# Microcontroleur.net
KiCad netlist of a schematic drawn in Altium Designer
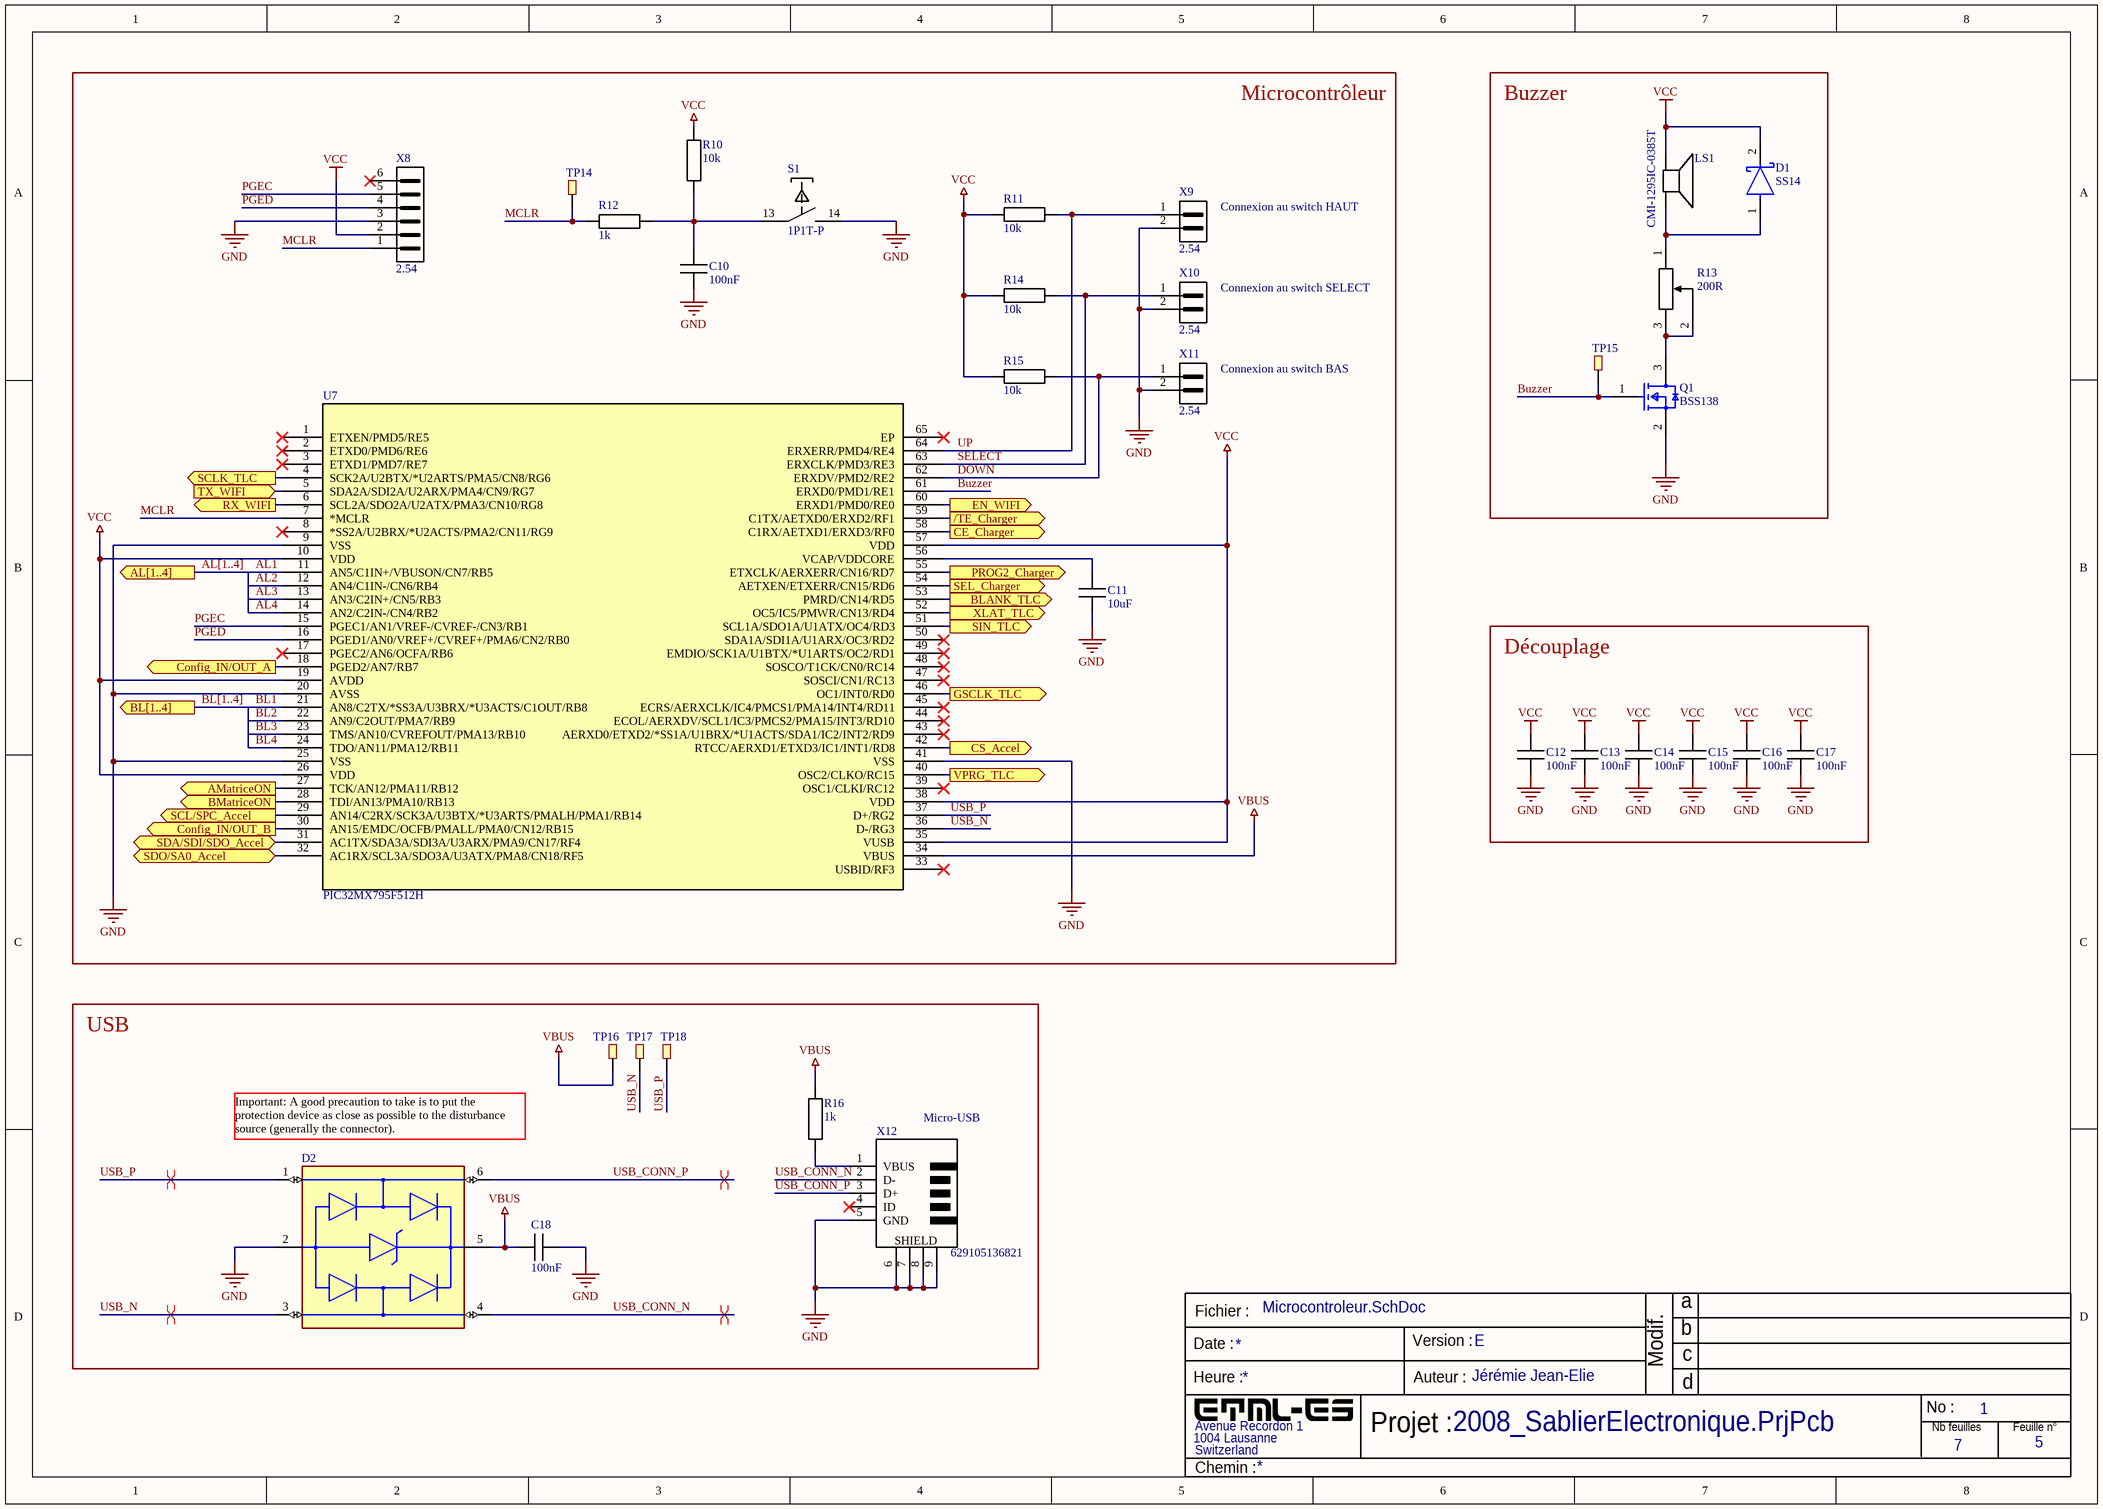
[diagram p0: Microcontroleur.SchDoc]

(export (version "E")
  (design (tool "Eeschema 10.0.6"))
  (components
    (comp (ref "C10")
      (value "100nF")
      (footprint "CAPC1608X08M")
      (description "CAPC 100nF X7R 50V 10% 1608 (0603 INCH)")
      (fields (field (name "VOLTAGE") "50V") (field (name "MANUFACTURER") "TDK"))
      (libsource (lib "ETML-ES") (part "CAP"))
    )
    (comp (ref "C11")
      (value "10uF")
      (footprint "CAPC1608X08M")
      (description "CAPC 10uF X5R 10V 20% 1608 (0603 INCH)")
      (fields (field (name "TOLERANCE") "±20%") (field (name "MANUFACTURER") "TDK"))
      (libsource (lib "ETML-ES") (part "CAP"))
    )
    (comp (ref "C12")
      (value "100nF")
      (footprint "CAPC1608X08M")
      (description "CAPC 100nF X7R 50V 10% 1608 (0603 INCH)")
      (fields (field (name "VOLTAGE") "50V") (field (name "MANUFACTURER") "TDK"))
      (libsource (lib "ETML-ES") (part "CAP"))
    )
    (comp (ref "C13")
      (value "100nF")
      (footprint "CAPC1608X08M")
      (description "CAPC 100nF X7R 50V 10% 1608 (0603 INCH)")
      (fields (field (name "VOLTAGE") "50V") (field (name "MANUFACTURER") "TDK"))
      (libsource (lib "ETML-ES") (part "CAP"))
    )
    (comp (ref "C14")
      (value "100nF")
      (footprint "CAPC1608X08M")
      (description "CAPC 100nF X7R 50V 10% 1608 (0603 INCH)")
      (fields (field (name "VOLTAGE") "50V") (field (name "MANUFACTURER") "TDK"))
      (libsource (lib "ETML-ES") (part "CAP"))
    )
    (comp (ref "C15")
      (value "100nF")
      (footprint "CAPC1608X08M")
      (description "CAPC 100nF X7R 50V 10% 1608 (0603 INCH)")
      (fields (field (name "VOLTAGE") "50V") (field (name "MANUFACTURER") "TDK"))
      (libsource (lib "ETML-ES") (part "CAP"))
    )
    (comp (ref "C16")
      (value "100nF")
      (footprint "CAPC1608X08M")
      (description "CAPC 100nF X7R 50V 10% 1608 (0603 INCH)")
      (fields (field (name "VOLTAGE") "50V") (field (name "MANUFACTURER") "TDK"))
      (libsource (lib "ETML-ES") (part "CAP"))
    )
    (comp (ref "C17")
      (value "100nF")
      (footprint "CAPC1608X08M")
      (description "CAPC 100nF X7R 50V 10% 1608 (0603 INCH)")
      (fields (field (name "VOLTAGE") "50V") (field (name "MANUFACTURER") "TDK"))
      (libsource (lib "ETML-ES") (part "CAP"))
    )
    (comp (ref "C18")
      (value "100nF")
      (footprint "CAPC1608X08M")
      (description "CAPC 100nF X7R 50V 10% 1608 (0603 INCH)")
      (fields (field (name "VOLTAGE") "50V") (field (name "MANUFACTURER") "TDK"))
      (libsource (lib "ETML-ES") (part "CAP"))
    )
    (comp (ref "D1")
      (value "SS14")
      (footprint "FP-403AE-MFG")
      (description "DIODE SCHOTTKY 40V 1A SMA")
      (fields
        (field (name "MANUFACTURER") "ON Semiconductor")
        (field (name "OCTOPART") "https://octopart.com/ss14-on+semiconductor-29205033")
      )
      (libsource (lib "Altium Content Vault") (part "360ad2f4ac25a952324d13796385471"))
    )
    (comp (ref "D2")
      (value "USBLC6-2P6")
      (footprint "SOT95P280X145-6N")
      (libsource (lib "2008_SablierElectronique_SCHLIB") (part "USBLC6-2P6"))
    )
    (comp (ref "LS1")
      (value "CMI-1295IC-0385T")
      (footprint "CMI-1295IC-0385T")
      (description "12 mm, 3 Vdc, 85 dB, Through Hole, Driving Circuit, Magnetic Audio Indicator Buzzer")
      (libsource (lib "Schlib1") (part "CMI-1295IC-0385T"))
    )
    (comp (ref "Q1")
      (value "BSS138")
      (footprint "FP-318-08-IPC_B")
      (description "MOSFET N-CH 50V 220MA SOT-23")
      (libsource (lib "Altium Content Vault") (part "3b9c635fedb024a5347a57b145af9cc"))
    )
    (comp (ref "R10")
      (value "10k")
      (footprint "RESC1608X06M")
      (description "RES 10kohm  ±1% 0.1W  1608 (0603 INCH)")
      (fields (field (name "TOLERANCE") "±1%") (field (name "VOLTAGE") "75V"))
      (libsource (lib "ETML-ES") (part "RES"))
    )
    (comp (ref "R11")
      (value "10k")
      (footprint "RESC1608X06M")
      (description "RES 10kohm  ±1% 0.1W  1608 (0603 INCH)")
      (fields (field (name "TOLERANCE") "±1%") (field (name "VOLTAGE") "75V"))
      (libsource (lib "ETML-ES") (part "RES"))
    )
    (comp (ref "R12")
      (value "1k")
      (footprint "RESC1608X06M")
      (description "RES 1.0kohm  ±1% 0.1W  1608 (0603 INCH)")
      (fields (field (name "POWER") "0.1W") (field (name "TOLERANCE") "±1%"))
      (libsource (lib "ETML-ES") (part "RES"))
    )
    (comp (ref "R13") (value "200R") (footprint "POT_200r") (libsource (lib "Schlib1") (part "Pot_200R")))
    (comp (ref "R14")
      (value "10k")
      (footprint "RESC1608X06M")
      (description "RES 10kohm  ±1% 0.1W  1608 (0603 INCH)")
      (fields (field (name "TOLERANCE") "±1%") (field (name "VOLTAGE") "75V"))
      (libsource (lib "ETML-ES") (part "RES"))
    )
    (comp (ref "R15")
      (value "10k")
      (footprint "RESC1608X06M")
      (description "RES 10kohm  ±1% 0.1W  1608 (0603 INCH)")
      (fields (field (name "TOLERANCE") "±1%") (field (name "VOLTAGE") "75V"))
      (libsource (lib "ETML-ES") (part "RES"))
    )
    (comp (ref "R16")
      (value "1k")
      (footprint "RESC1608X06M")
      (description "RES 1.0kohm  ±1% 0.1W  1608 (0603 INCH)")
      (fields (field (name "POWER") "0.1W") (field (name "TOLERANCE") "±1%"))
      (libsource (lib "ETML-ES") (part "RES"))
    )
    (comp (ref "S1")
      (value "1P1T-P")
      (footprint "TE_1825910-6")
      (description "SW 600X600X500 24V 50mA THT")
      (fields (field (name "VOLTAGE") "24V") (field (name "MANUFACTURER") "TE Connectivity"))
      (libsource (lib "ETML-ES") (part "SWI-1P1T-P"))
    )
    (comp (ref "TP14")
      (value "TestPoint")
      (footprint "KEYSTONE_5019")
      (libsource (lib "Schlib1") (part "TestPoint"))
    )
    (comp (ref "TP15")
      (value "TestPoint")
      (footprint "KEYSTONE_5019")
      (libsource (lib "Schlib1") (part "TestPoint"))
    )
    (comp (ref "TP16")
      (value "TestPoint")
      (footprint "KEYSTONE_5019")
      (libsource (lib "Schlib1") (part "TestPoint"))
    )
    (comp (ref "TP17")
      (value "TestPoint")
      (footprint "KEYSTONE_5019")
      (libsource (lib "Schlib1") (part "TestPoint"))
    )
    (comp (ref "TP18")
      (value "TestPoint")
      (footprint "KEYSTONE_5019")
      (libsource (lib "Schlib1") (part "TestPoint"))
    )
    (comp (ref "U7")
      (value "PIC32MX795F512H")
      (footprint "TQFP64_10x10MC_MCH")
      (libsource (lib "Schlib1") (part "PIC32MX795F512H"))
    )
    (comp (ref "X8")
      (value "2.54")
      (footprint "PIN-1x06-2.54")
      (description "PIN HEADER 2.54 1x06")
      (fields (field (name "MANUFACTURER") "Würth Electronik") (field (name "VOLTAGE") "250V"))
      (libsource (lib "ETML-ES") (part "CON-PIN-1x06"))
    )
    (comp (ref "X9")
      (value "2.54")
      (footprint "PIN-1x02-2.54")
      (description "PIN HEADER 2.54 1x02")
      (fields (field (name "MANUFACTURER") "Würth Electronik") (field (name "VOLTAGE") "250V"))
      (libsource (lib "ETML-ES") (part "CON-PIN-1x02"))
    )
    (comp (ref "X10")
      (value "2.54")
      (footprint "PIN-1x02-2.54")
      (description "PIN HEADER 2.54 1x02")
      (fields (field (name "MANUFACTURER") "Würth Electronik") (field (name "VOLTAGE") "250V"))
      (libsource (lib "ETML-ES") (part "CON-PIN-1x02"))
    )
    (comp (ref "X11")
      (value "2.54")
      (footprint "PIN-1x02-2.54")
      (description "PIN HEADER 2.54 1x02")
      (fields (field (name "MANUFACTURER") "Würth Electronik") (field (name "VOLTAGE") "250V"))
      (libsource (lib "ETML-ES") (part "CON-PIN-1x02"))
    )
    (comp (ref "X12")
      (value "629105136821")
      (footprint "WE_629105136821")
      (description "USB MICRO 5P Horizontal SMT")
      (fields (field (name "MANUFACTURER") "Würth Electronik"))
      (libsource (lib "ETML-ES") (part "USB_MINI_MICRO_B_F"))
    )
  )
  (nets
    (net (code "1") (name "/AL1") (class "Default")
      (node (ref "U7") (pin "11") (pinfunction "AN5/C1IN+/VBUSON/CN7/RB5_11") (pintype "passive"))
    )
    (net (code "2") (name "/AL2") (class "Default")
      (node (ref "U7") (pin "12") (pinfunction "AN4/C1IN-/CN6/RB4_12") (pintype "passive"))
    )
    (net (code "3") (name "/AL3") (class "Default")
      (node (ref "U7") (pin "13") (pinfunction "AN3/C2IN+/CN5/RB3_13") (pintype "passive"))
    )
    (net (code "4") (name "/AL4") (class "Default")
      (node (ref "U7") (pin "14") (pinfunction "AN2/C2IN-/CN4/RB2_14") (pintype "passive"))
    )
    (net (code "6") (name "/AMatriceON") (class "Default")
      (node (ref "U7") (pin "27") (pinfunction "TCK/AN12/PMA11/RB12_27") (pintype "passive"))
    )
    (net (code "7") (name "/BL1") (class "Default")
      (node (ref "U7") (pin "21") (pinfunction "AN8/C2TX/*SS3A/U3BRX/*U3ACTS/C1OUT/RB8_21") (pintype "passive"))
    )
    (net (code "8") (name "/BL2") (class "Default")
      (node (ref "U7") (pin "22") (pinfunction "AN9/C2OUT/PMA7/RB9_22") (pintype "passive"))
    )
    (net (code "9") (name "/BL3") (class "Default")
      (node (ref "U7") (pin "23") (pinfunction "TMS/AN10/CVREFOUT/PMA13/RB10_23") (pintype "passive"))
    )
    (net (code "10") (name "/BL4") (class "Default")
      (node (ref "U7") (pin "24") (pinfunction "TDO/AN11/PMA12/RB11_24") (pintype "passive"))
    )
    (net (code "11") (name "/BLANK_TLC") (class "Default")
      (node (ref "U7") (pin "53") (pinfunction "PMRD/CN14/RD5_53") (pintype "passive"))
    )
    (net (code "13") (name "/BMatriceON") (class "Default")
      (node (ref "U7") (pin "28") (pinfunction "TDI/AN13/PMA10/RB13_28") (pintype "passive"))
    )
    (net (code "14") (name "/Buzzer") (class "Default")
      (node (ref "Q1") (pin "1") (pinfunction "G_1") (pintype "passive"))
      (node (ref "TP15") (pin "1") (pinfunction "1_1") (pintype "passive"))
      (node (ref "U7") (pin "61") (pinfunction "ERXD0/PMD1/RE1_61") (pintype "passive"))
    )
    (net (code "15") (name "/CE_Charger") (class "Default")
      (node (ref "U7") (pin "58") (pinfunction "C1RX/AETXD1/ERXD3/RF0_58") (pintype "passive"))
    )
    (net (code "16") (name "/CS_Accel") (class "Default")
      (node (ref "U7") (pin "42") (pinfunction "RTCC/AERXD1/ETXD3/IC1/INT1/RD8_42") (pintype "passive"))
    )
    (net (code "17") (name "/Config_IN{slash}OUT_A") (class "Default")
      (node (ref "U7") (pin "18") (pinfunction "PGED2/AN7/RB7_18") (pintype "passive"))
    )
    (net (code "18") (name "/Config_IN{slash}OUT_B") (class "Default")
      (node (ref "U7") (pin "30") (pinfunction "AN15/EMDC/OCFB/PMALL/PMA0/CN12/RB15_30") (pintype "passive"))
    )
    (net (code "19") (name "/DOWN") (class "Default")
      (node (ref "R15") (pin "1") (pinfunction "1_1") (pintype "passive"))
      (node (ref "U7") (pin "62") (pinfunction "ERXDV/PMD2/RE2_62") (pintype "passive"))
      (node (ref "X11") (pin "1") (pinfunction "1_1") (pintype "passive"))
    )
    (net (code "20") (name "/EN_WIFI") (class "Default")
      (node (ref "U7") (pin "60") (pinfunction "ERXD1/PMD0/RE0_60") (pintype "passive"))
    )
    (net (code "21") (name "/GSCLK_TLC") (class "Default")
      (node (ref "U7") (pin "46") (pinfunction "OC1/INT0/RD0_46") (pintype "passive"))
    )
    (net (code "22") (name "/MCLR") (class "Default")
      (node (ref "R12") (pin "1") (pinfunction "1_1") (pintype "passive"))
      (node (ref "TP14") (pin "1") (pinfunction "1_1") (pintype "passive"))
      (node (ref "U7") (pin "7") (pinfunction "*MCLR_7") (pintype "passive"))
      (node (ref "X8") (pin "1") (pinfunction "1_1") (pintype "passive"))
    )
    (net (code "23") (name "/PGEC") (class "Default")
      (node (ref "U7") (pin "15") (pinfunction "PGEC1/AN1/VREF-/CVREF-/CN3/RB1_15") (pintype "passive"))
      (node (ref "X8") (pin "5") (pinfunction "5_5") (pintype "passive"))
    )
    (net (code "24") (name "/PGED") (class "Default")
      (node (ref "U7") (pin "16") (pinfunction "PGED1/AN0/VREF+/CVREF+/PMA6/CN2/RB0_16") (pintype "passive"))
      (node (ref "X8") (pin "4") (pinfunction "4_4") (pintype "passive"))
    )
    (net (code "25") (name "/PROG2_Charger") (class "Default")
      (node (ref "U7") (pin "55") (pinfunction "ETXCLK/AERXERR/CN16/RD7_55") (pintype "passive"))
    )
    (net (code "26") (name "/RX_WIFI") (class "Default")
      (node (ref "U7") (pin "6") (pinfunction "SCL2A/SDO2A/U2ATX/PMA3/CN10/RG8_6") (pintype "passive"))
    )
    (net (code "27") (name "/SCLK_TLC") (class "Default")
      (node (ref "U7") (pin "4") (pinfunction "SCK2A/U2BTX/*U2ARTS/PMA5/CN8/RG6_4") (pintype "passive"))
    )
    (net (code "28") (name "/SCL{slash}SPC_Accel") (class "Default")
      (node (ref "U7") (pin "29") (pinfunction "AN14/C2RX/SCK3A/U3BTX/*U3ARTS/PMALH/PMA1/RB14_29") (pintype "passive"))
    )
    (net (code "29") (name "/SDA{slash}SDI{slash}SDO_Accel") (class "Default")
      (node (ref "U7") (pin "31") (pinfunction "AC1TX/SDA3A/SDI3A/U3ARX/PMA9/CN17/RF4_31") (pintype "passive"))
    )
    (net (code "30") (name "/SDO{slash}SA0_Accel") (class "Default")
      (node (ref "U7") (pin "32") (pinfunction "AC1RX/SCL3A/SDO3A/U3ATX/PMA8/CN18/RF5_32") (pintype "passive"))
    )
    (net (code "31") (name "/SELECT") (class "Default")
      (node (ref "R14") (pin "1") (pinfunction "1_1") (pintype "passive"))
      (node (ref "U7") (pin "63") (pinfunction "ERXCLK/PMD3/RE3_63") (pintype "passive"))
      (node (ref "X10") (pin "1") (pinfunction "1_1") (pintype "passive"))
    )
    (net (code "32") (name "/SEL_Charger") (class "Default")
      (node (ref "U7") (pin "54") (pinfunction "AETXEN/ETXERR/CN15/RD6_54") (pintype "passive"))
    )
    (net (code "33") (name "/SIN_TLC") (class "Default")
      (node (ref "U7") (pin "51") (pinfunction "SCL1A/SDO1A/U1ATX/OC4/RD3_51") (pintype "passive"))
    )
    (net (code "34") (name "/TX_WIFI") (class "Default")
      (node (ref "U7") (pin "5") (pinfunction "SDA2A/SDI2A/U2ARX/PMA4/CN9/RG7_5") (pintype "passive"))
    )
    (net (code "35") (name "/UP") (class "Default")
      (node (ref "R11") (pin "1") (pinfunction "1_1") (pintype "passive"))
      (node (ref "U7") (pin "64") (pinfunction "ERXERR/PMD4/RE4_64") (pintype "passive"))
      (node (ref "X9") (pin "1") (pinfunction "1_1") (pintype "passive"))
    )
    (net (code "36") (name "/USB_CONN_N") (class "Default")
      (node (ref "D2") (pin "4") (pinfunction "I/O2_4") (pintype "bidirectional"))
      (node (ref "X12") (pin "2") (pinfunction "D-_2") (pintype "passive"))
    )
    (net (code "37") (name "/USB_CONN_P") (class "Default")
      (node (ref "D2") (pin "6") (pinfunction "I/O1_6") (pintype "bidirectional"))
      (node (ref "X12") (pin "3") (pinfunction "D+_3") (pintype "passive"))
    )
    (net (code "38") (name "/USB_N") (class "Default")
      (node (ref "D2") (pin "3") (pinfunction "I/O2_3") (pintype "bidirectional"))
      (node (ref "TP17") (pin "1") (pinfunction "1_1") (pintype "passive"))
      (node (ref "U7") (pin "36") (pinfunction "D-/RG3_36") (pintype "passive"))
    )
    (net (code "39") (name "/USB_P") (class "Default")
      (node (ref "D2") (pin "1") (pinfunction "I/O1_1") (pintype "bidirectional"))
      (node (ref "TP18") (pin "1") (pinfunction "1_1") (pintype "passive"))
      (node (ref "U7") (pin "37") (pinfunction "D+/RG2_37") (pintype "passive"))
    )
    (net (code "40") (name "/VPRG_TLC") (class "Default")
      (node (ref "U7") (pin "40") (pinfunction "OSC2/CLKO/RC15_40") (pintype "passive"))
    )
    (net (code "41") (name "/XLAT_TLC") (class "Default")
      (node (ref "U7") (pin "52") (pinfunction "OC5/IC5/PMWR/CN13/RD4_52") (pintype "passive"))
    )
    (net (code "42") (name "/{slash}TE_Charger") (class "Default")
      (node (ref "U7") (pin "59") (pinfunction "C1TX/AETXD0/ERXD2/RF1_59") (pintype "passive"))
    )
    (net (code "43") (name "GND") (class "Default")
      (node (ref "C10") (pin "1") (pinfunction "1_1") (pintype "passive"))
      (node (ref "C11") (pin "1") (pinfunction "1_1") (pintype "passive"))
      (node (ref "C12") (pin "1") (pinfunction "1_1") (pintype "passive"))
      (node (ref "C13") (pin "1") (pinfunction "1_1") (pintype "passive"))
      (node (ref "C14") (pin "1") (pinfunction "1_1") (pintype "passive"))
      (node (ref "C15") (pin "1") (pinfunction "1_1") (pintype "passive"))
      (node (ref "C16") (pin "1") (pinfunction "1_1") (pintype "passive"))
      (node (ref "C17") (pin "1") (pinfunction "1_1") (pintype "passive"))
      (node (ref "C18") (pin "2") (pinfunction "2_2") (pintype "passive"))
      (node (ref "D2") (pin "2") (pinfunction "GND_2") (pintype "power_in"))
      (node (ref "Q1") (pin "2") (pinfunction "S_2") (pintype "passive"))
      (node (ref "S1") (pin "14") (pinfunction "14_14") (pintype "passive"))
      (node (ref "U7") (pin "20") (pinfunction "AVSS_20") (pintype "passive"))
      (node (ref "U7") (pin "25") (pinfunction "VSS_25") (pintype "passive"))
      (node (ref "U7") (pin "41") (pinfunction "VSS_41") (pintype "passive"))
      (node (ref "U7") (pin "9") (pinfunction "VSS_9") (pintype "passive"))
      (node (ref "X10") (pin "2") (pinfunction "2_2") (pintype "passive"))
      (node (ref "X11") (pin "2") (pinfunction "2_2") (pintype "passive"))
      (node (ref "X12") (pin "5") (pinfunction "GND_5") (pintype "passive"))
      (node (ref "X12") (pin "6") (pinfunction "SHIELD_6") (pintype "passive"))
      (node (ref "X12") (pin "7") (pinfunction "SHIELD_7") (pintype "passive"))
      (node (ref "X12") (pin "8") (pinfunction "SHIELD_8") (pintype "passive"))
      (node (ref "X12") (pin "9") (pinfunction "SHIELD_9") (pintype "passive"))
      (node (ref "X8") (pin "3") (pinfunction "3_3") (pintype "passive"))
      (node (ref "X9") (pin "2") (pinfunction "2_2") (pintype "passive"))
    )
    (net (code "44") (name "Net-(C10-Pad2)") (class "Default")
      (node (ref "C10") (pin "2") (pinfunction "2_2") (pintype "passive"))
      (node (ref "R10") (pin "1") (pinfunction "1_1") (pintype "passive"))
      (node (ref "R12") (pin "2") (pinfunction "2_2") (pintype "passive"))
      (node (ref "S1") (pin "13") (pinfunction "13_13") (pintype "passive"))
    )
    (net (code "45") (name "Net-(D1-A)") (class "Default")
      (node (ref "D1") (pin "1") (pinfunction "A_1") (pintype "passive"))
      (node (ref "LS1") (pin "2") (pinfunction "-_2") (pintype "passive"))
      (node (ref "R13") (pin "1") (pinfunction "1_1") (pintype "passive"))
    )
    (net (code "46") (name "Net-(Q1-D)") (class "Default")
      (node (ref "Q1") (pin "3") (pinfunction "D_3") (pintype "passive"))
      (node (ref "R13") (pin "2") (pinfunction "2_2") (pintype "passive"))
      (node (ref "R13") (pin "3") (pinfunction "3_3") (pintype "passive"))
    )
    (net (code "47") (name "Net-(U7-VCAP{slash}VDDCORE)") (class "Default")
      (node (ref "C11") (pin "2") (pinfunction "2_2") (pintype "passive"))
      (node (ref "U7") (pin "56") (pinfunction "VCAP/VDDCORE_56") (pintype "passive"))
    )
    (net (code "48") (name "Net-(X12-VBUS)") (class "Default")
      (node (ref "R16") (pin "1") (pinfunction "1_1") (pintype "passive"))
      (node (ref "X12") (pin "1") (pinfunction "VBUS_1") (pintype "passive"))
    )
    (net (code "49") (name "VBUS") (class "Default")
      (node (ref "C18") (pin "1") (pinfunction "1_1") (pintype "passive"))
      (node (ref "D2") (pin "5") (pinfunction "VBUS_5") (pintype "power_in"))
      (node (ref "R16") (pin "2") (pinfunction "2_2") (pintype "passive"))
      (node (ref "TP16") (pin "1") (pinfunction "1_1") (pintype "passive"))
      (node (ref "U7") (pin "34") (pinfunction "VBUS_34") (pintype "passive"))
    )
    (net (code "50") (name "VCC") (class "Default")
      (node (ref "C12") (pin "2") (pinfunction "2_2") (pintype "passive"))
      (node (ref "C13") (pin "2") (pinfunction "2_2") (pintype "passive"))
      (node (ref "C14") (pin "2") (pinfunction "2_2") (pintype "passive"))
      (node (ref "C15") (pin "2") (pinfunction "2_2") (pintype "passive"))
      (node (ref "C16") (pin "2") (pinfunction "2_2") (pintype "passive"))
      (node (ref "C17") (pin "2") (pinfunction "2_2") (pintype "passive"))
      (node (ref "D1") (pin "2") (pinfunction "C_2") (pintype "passive"))
      (node (ref "LS1") (pin "1") (pinfunction "+_1") (pintype "passive"))
      (node (ref "R10") (pin "2") (pinfunction "2_2") (pintype "passive"))
      (node (ref "R11") (pin "2") (pinfunction "2_2") (pintype "passive"))
      (node (ref "R14") (pin "2") (pinfunction "2_2") (pintype "passive"))
      (node (ref "R15") (pin "2") (pinfunction "2_2") (pintype "passive"))
      (node (ref "U7") (pin "10") (pinfunction "VDD_10") (pintype "passive"))
      (node (ref "U7") (pin "19") (pinfunction "AVDD_19") (pintype "passive"))
      (node (ref "U7") (pin "26") (pinfunction "VDD_26") (pintype "passive"))
      (node (ref "U7") (pin "35") (pinfunction "VUSB_35") (pintype "passive"))
      (node (ref "U7") (pin "38") (pinfunction "VDD_38") (pintype "passive"))
      (node (ref "U7") (pin "57") (pinfunction "VDD_57") (pintype "passive"))
      (node (ref "X8") (pin "2") (pinfunction "2_2") (pintype "passive"))
    )
    (net (code "51") (name "unconnected-(U7-*SS2A{slash}U2BRX{slash}*U2ACTS{slash}PMA2{slash}CN11{slash}RG9-Pad8)") (class "Default")
      (node (ref "U7") (pin "8") (pinfunction "*SS2A/U2BRX/*U2ACTS/PMA2/CN11/RG9_8") (pintype "passive+no_connect"))
    )
    (net (code "52") (name "unconnected-(U7-AERXD0{slash}ETXD2{slash}*SS1A{slash}U1BRX{slash}*U1ACTS{slash}SDA1{slash}IC2{slash}INT2{slash}RD9-Pad43)") (class "Default")
      (node (ref "U7") (pin "43") (pinfunction "AERXD0/ETXD2/*SS1A/U1BRX/*U1ACTS/SDA1/IC2/INT2/RD9_43") (pintype "passive+no_connect"))
    )
    (net (code "53") (name "unconnected-(U7-ECOL{slash}AERXDV{slash}SCL1{slash}IC3{slash}PMCS2{slash}PMA15{slash}INT3{slash}RD10-Pad44)") (class "Default")
      (node (ref "U7") (pin "44") (pinfunction "ECOL/AERXDV/SCL1/IC3/PMCS2/PMA15/INT3/RD10_44") (pintype "passive+no_connect"))
    )
    (net (code "54") (name "unconnected-(U7-ECRS{slash}AERXCLK{slash}IC4{slash}PMCS1{slash}PMA14{slash}INT4{slash}RD11-Pad45)") (class "Default")
      (node (ref "U7") (pin "45") (pinfunction "ECRS/AERXCLK/IC4/PMCS1/PMA14/INT4/RD11_45") (pintype "passive+no_connect"))
    )
    (net (code "55") (name "unconnected-(U7-EMDIO{slash}SCK1A{slash}U1BTX{slash}*U1ARTS{slash}OC2{slash}RD1-Pad49)") (class "Default")
      (node (ref "U7") (pin "49") (pinfunction "EMDIO/SCK1A/U1BTX/*U1ARTS/OC2/RD1_49") (pintype "passive+no_connect"))
    )
    (net (code "56") (name "unconnected-(U7-EP-Pad65)") (class "Default")
      (node (ref "U7") (pin "65") (pinfunction "EP_65") (pintype "passive+no_connect"))
    )
    (net (code "57") (name "unconnected-(U7-ETXD0{slash}PMD6{slash}RE6-Pad2)") (class "Default")
      (node (ref "U7") (pin "2") (pinfunction "ETXD0/PMD6/RE6_2") (pintype "passive+no_connect"))
    )
    (net (code "58") (name "unconnected-(U7-ETXD1{slash}PMD7{slash}RE7-Pad3)") (class "Default")
      (node (ref "U7") (pin "3") (pinfunction "ETXD1/PMD7/RE7_3") (pintype "passive+no_connect"))
    )
    (net (code "59") (name "unconnected-(U7-ETXEN{slash}PMD5{slash}RE5-Pad1)") (class "Default")
      (node (ref "U7") (pin "1") (pinfunction "ETXEN/PMD5/RE5_1") (pintype "passive+no_connect"))
    )
    (net (code "60") (name "unconnected-(U7-OSC1{slash}CLKI{slash}RC12-Pad39)") (class "Default")
      (node (ref "U7") (pin "39") (pinfunction "OSC1/CLKI/RC12_39") (pintype "passive+no_connect"))
    )
    (net (code "61") (name "unconnected-(U7-PGEC2{slash}AN6{slash}OCFA{slash}RB6-Pad17)") (class "Default")
      (node (ref "U7") (pin "17") (pinfunction "PGEC2/AN6/OCFA/RB6_17") (pintype "passive+no_connect"))
    )
    (net (code "62") (name "unconnected-(U7-SDA1A{slash}SDI1A{slash}U1ARX{slash}OC3{slash}RD2-Pad50)") (class "Default")
      (node (ref "U7") (pin "50") (pinfunction "SDA1A/SDI1A/U1ARX/OC3/RD2_50") (pintype "passive+no_connect"))
    )
    (net (code "63") (name "unconnected-(U7-SOSCI{slash}CN1{slash}RC13-Pad47)") (class "Default")
      (node (ref "U7") (pin "47") (pinfunction "SOSCI/CN1/RC13_47") (pintype "passive+no_connect"))
    )
    (net (code "64") (name "unconnected-(U7-SOSCO{slash}T1CK{slash}CN0{slash}RC14-Pad48)") (class "Default")
      (node (ref "U7") (pin "48") (pinfunction "SOSCO/T1CK/CN0/RC14_48") (pintype "passive+no_connect"))
    )
    (net (code "65") (name "unconnected-(U7-USBID{slash}RF3-Pad33)") (class "Default")
      (node (ref "U7") (pin "33") (pinfunction "USBID/RF3_33") (pintype "passive+no_connect"))
    )
    (net (code "66") (name "unconnected-(X8-Pad6)") (class "Default")
      (node (ref "X8") (pin "6") (pinfunction "6_6") (pintype "passive+no_connect"))
    )
    (net (code "67") (name "unconnected-(X12-ID-Pad4)") (class "Default")
      (node (ref "X12") (pin "4") (pinfunction "ID_4") (pintype "passive+no_connect"))
    )
  )
)
